# ocb03.net
KiCad netlist of a schematic drawn in EAGLE
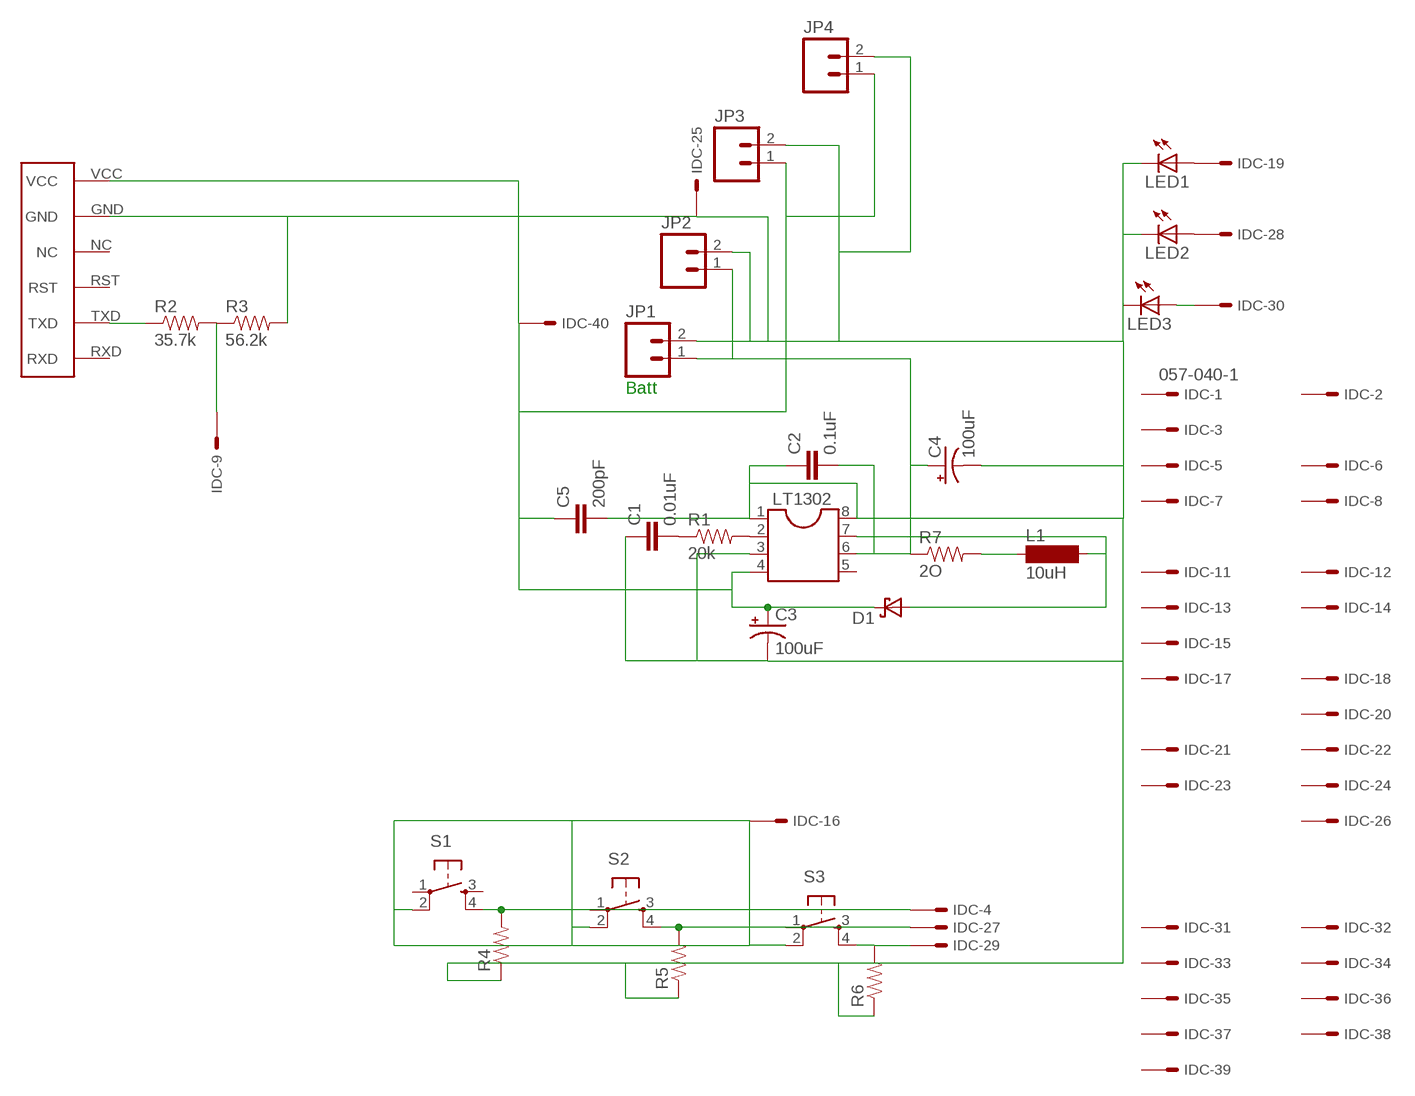
[diagram p0: schematic, sheet 1]

(export (version "E")
  (design (tool "Eeschema 10.0.6"))
  (components
    (comp (ref "C1")
      (value "0.01uF")
      (footprint "eagle-import:CAP-PTH-SMALL")
      (libsource (lib "eagle-import") (part "CAPPTH"))
    )
    (comp (ref "C2")
      (value "0.1uF")
      (footprint "eagle-import:CAP-PTH-SMALL")
      (libsource (lib "eagle-import") (part "CAPPTH"))
    )
    (comp (ref "C3")
      (value "100uF")
      (footprint "eagle-import:CPOL-RADIAL-100UF-25V")
      (libsource (lib "eagle-import") (part "CAP_POLPTH1"))
    )
    (comp (ref "C4")
      (value "100uF")
      (footprint "eagle-import:CPOL-RADIAL-100UF-25V")
      (libsource (lib "eagle-import") (part "CAP_POLPTH1"))
    )
    (comp (ref "C5")
      (value "200pF")
      (footprint "eagle-import:CAP-PTH-SMALL")
      (libsource (lib "eagle-import") (part "CAPPTH"))
    )
    (comp (ref "D1")
      (value "DS_E2L")
      (footprint "eagle-import:E2LINE")
      (libsource (lib "eagle-import") (part "DS_E2L"))
    )
    (comp (ref "IDC")
      (value "057-040-1")
      (footprint "eagle-import:057-040-1")
      (libsource (lib "eagle-import") (part "057-040-1"))
    )
    (comp (ref "JP1")
      (value "M02JST-PTH-2")
      (footprint "eagle-import:JST-2-PTH")
      (libsource (lib "eagle-import") (part "M02JST-PTH-2"))
    )
    (comp (ref "JP2")
      (value "M02JST-PTH-2")
      (footprint "eagle-import:JST-2-PTH")
      (libsource (lib "eagle-import") (part "M02JST-PTH-2"))
    )
    (comp (ref "JP3")
      (value "M02JST-PTH-2")
      (footprint "eagle-import:JST-2-PTH")
      (libsource (lib "eagle-import") (part "M02JST-PTH-2"))
    )
    (comp (ref "JP4")
      (value "M02JST-PTH-2")
      (footprint "eagle-import:JST-2-PTH")
      (libsource (lib "eagle-import") (part "M02JST-PTH-2"))
    )
    (comp (ref "L1")
      (value "10uH")
      (footprint "eagle-import:BS11")
      (libsource (lib "eagle-import") (part "BS11"))
    )
    (comp (ref "LED1")
      (value "LED5MM")
      (footprint "eagle-import:LED5MM")
      (libsource (lib "eagle-import") (part "LED5MM"))
    )
    (comp (ref "LED2")
      (value "LED5MM")
      (footprint "eagle-import:LED5MM")
      (libsource (lib "eagle-import") (part "LED5MM"))
    )
    (comp (ref "LED3")
      (value "LED5MM")
      (footprint "eagle-import:LED5MM")
      (libsource (lib "eagle-import") (part "LED5MM"))
    )
    (comp (ref "LT1302")
      (value "DIL8")
      (footprint "eagle-import:DIL08")
      (libsource (lib "eagle-import") (part "DIL8"))
    )
    (comp (ref "R1")
      (value "20k")
      (footprint "eagle-import:AXIAL-0.4")
      (libsource (lib "eagle-import") (part "RESISTORPTH-1/4W"))
    )
    (comp (ref "R2")
      (value "35.7k")
      (footprint "eagle-import:AXIAL-0.4")
      (libsource (lib "eagle-import") (part "RESISTORPTH-1/4W"))
    )
    (comp (ref "R3")
      (value "56.2k")
      (footprint "eagle-import:AXIAL-0.4")
      (libsource (lib "eagle-import") (part "RESISTORPTH-1/4W"))
    )
    (comp (ref "R4")
      (value "RESISTORPTH-1/4W")
      (footprint "eagle-import:AXIAL-0.4")
      (libsource (lib "eagle-import") (part "RESISTORPTH-1/4W"))
    )
    (comp (ref "R5")
      (value "RESISTORPTH-1/4W")
      (footprint "eagle-import:AXIAL-0.4")
      (libsource (lib "eagle-import") (part "RESISTORPTH-1/4W"))
    )
    (comp (ref "R6")
      (value "RESISTORPTH-1/4W")
      (footprint "eagle-import:AXIAL-0.4")
      (libsource (lib "eagle-import") (part "RESISTORPTH-1/4W"))
    )
    (comp (ref "R7")
      (value "2O")
      (footprint "eagle-import:AXIAL-0.4")
      (libsource (lib "eagle-import") (part "RESISTORPTH-1/4W"))
    )
    (comp (ref "S1")
      (value "TAC_SWITCHPTH")
      (footprint "eagle-import:TACTILE-PTH")
      (libsource (lib "eagle-import") (part "TAC_SWITCHPTH"))
    )
    (comp (ref "S2")
      (value "TAC_SWITCHPTH")
      (footprint "eagle-import:TACTILE-PTH")
      (libsource (lib "eagle-import") (part "TAC_SWITCHPTH"))
    )
    (comp (ref "S3")
      (value "TAC_SWITCHPTH")
      (footprint "eagle-import:TACTILE-PTH")
      (libsource (lib "eagle-import") (part "TAC_SWITCHPTH"))
    )
    (comp (ref "U$2")
      (value "SKYLAB_LAB")
      (footprint "eagle-import:SKYLAB_GPS")
      (libsource (lib "eagle-import") (part "SKYLAB_LAB"))
    )
  )
  (nets
    (net (code "1") (name "Net-(C3-+)") (class "Default")
      (node (ref "C3") (pin "1") (pinfunction "+_1") (pintype "passive"))
      (node (ref "C5") (pin "1") (pinfunction "1_1") (pintype "passive"))
      (node (ref "D1") (pin "1") (pinfunction "K_1") (pintype "passive"))
      (node (ref "IDC") (pin "40") (pinfunction "S_40") (pintype "passive"))
      (node (ref "JP3") (pin "1") (pinfunction "1_1") (pintype "passive"))
      (node (ref "JP4") (pin "1") (pinfunction "1_1") (pintype "passive"))
      (node (ref "LT1302") (pin "4") (pinfunction "4_4") (pintype "passive"))
      (node (ref "U$2") (pin "VCC") (pinfunction "VCC_VCC") (pintype "bidirectional"))
    )
    (net (code "2") (name "Net-(C3--)") (class "Default")
      (node (ref "C1") (pin "1") (pinfunction "1_1") (pintype "passive"))
      (node (ref "C2") (pin "1") (pinfunction "1_1") (pintype "passive"))
      (node (ref "C3") (pin "2") (pinfunction "-_2") (pintype "passive"))
      (node (ref "C4") (pin "2") (pinfunction "-_2") (pintype "passive"))
      (node (ref "C5") (pin "2") (pinfunction "2_2") (pintype "passive"))
      (node (ref "IDC") (pin "25") (pinfunction "S_25") (pintype "passive"))
      (node (ref "JP1") (pin "2") (pinfunction "2_2") (pintype "passive"))
      (node (ref "JP2") (pin "2") (pinfunction "2_2") (pintype "passive"))
      (node (ref "JP3") (pin "2") (pinfunction "2_2") (pintype "passive"))
      (node (ref "JP4") (pin "2") (pinfunction "2_2") (pintype "passive"))
      (node (ref "LED1") (pin "K") (pinfunction "C_K") (pintype "passive"))
      (node (ref "LED2") (pin "K") (pinfunction "C_K") (pintype "passive"))
      (node (ref "LED3") (pin "K") (pinfunction "C_K") (pintype "passive"))
      (node (ref "LT1302") (pin "1") (pinfunction "1_1") (pintype "passive"))
      (node (ref "LT1302") (pin "3") (pinfunction "3_3") (pintype "passive"))
      (node (ref "LT1302") (pin "8") (pinfunction "8_8") (pintype "passive"))
      (node (ref "R3") (pin "P$2") (pinfunction "2_P$2") (pintype "passive"))
      (node (ref "R4") (pin "P$1") (pinfunction "1_P$1") (pintype "passive"))
      (node (ref "R5") (pin "P$1") (pinfunction "1_P$1") (pintype "passive"))
      (node (ref "R6") (pin "P$1") (pinfunction "1_P$1") (pintype "passive"))
      (node (ref "U$2") (pin "GND") (pinfunction "GND_GND") (pintype "bidirectional"))
    )
    (net (code "3") (name "Net-(C4-+)") (class "Default")
      (node (ref "C2") (pin "2") (pinfunction "2_2") (pintype "passive"))
      (node (ref "C4") (pin "1") (pinfunction "+_1") (pintype "passive"))
      (node (ref "JP1") (pin "1") (pinfunction "1_1") (pintype "passive"))
      (node (ref "JP2") (pin "1") (pinfunction "1_1") (pintype "passive"))
      (node (ref "LT1302") (pin "6") (pinfunction "6_6") (pintype "passive"))
      (node (ref "R7") (pin "P$1") (pinfunction "1_P$1") (pintype "passive"))
    )
    (net (code "4") (name "Net-(D1-A)") (class "Default")
      (node (ref "D1") (pin "2") (pinfunction "A_2") (pintype "passive"))
      (node (ref "L1") (pin "2") (pinfunction "2_2") (pintype "passive"))
      (node (ref "LT1302") (pin "7") (pinfunction "7_7") (pintype "passive"))
    )
    (net (code "5") (name "Net-(IDCAH-S)") (class "Default")
      (node (ref "IDC") (pin "4") (pinfunction "S_4") (pintype "passive"))
      (node (ref "R4") (pin "P$2") (pinfunction "2_P$2") (pintype "passive"))
      (node (ref "S1") (pin "4") (pinfunction "4_4") (pintype "passive"))
    )
    (net (code "6") (name "Net-(IDCAN-S)") (class "Default")
      (node (ref "IDC") (pin "9") (pinfunction "S_9") (pintype "passive"))
      (node (ref "R2") (pin "P$2") (pinfunction "2_P$2") (pintype "passive"))
      (node (ref "R3") (pin "P$1") (pinfunction "1_P$1") (pintype "passive"))
    )
    (net (code "7") (name "Net-(IDCH-S)") (class "Default")
      (node (ref "IDC") (pin "16") (pinfunction "S_16") (pintype "passive"))
      (node (ref "S1") (pin "2") (pinfunction "2_2") (pintype "passive"))
      (node (ref "S2") (pin "2") (pinfunction "2_2") (pintype "passive"))
      (node (ref "S3") (pin "2") (pinfunction "2_2") (pintype "passive"))
    )
    (net (code "8") (name "Net-(IDCK-S)") (class "Default")
      (node (ref "IDC") (pin "19") (pinfunction "S_19") (pintype "passive"))
      (node (ref "LED1") (pin "A") (pinfunction "A_A") (pintype "passive"))
    )
    (net (code "9") (name "Net-(IDCT-S)") (class "Default")
      (node (ref "IDC") (pin "27") (pinfunction "S_27") (pintype "passive"))
      (node (ref "R5") (pin "P$2") (pinfunction "2_P$2") (pintype "passive"))
      (node (ref "S2") (pin "4") (pinfunction "4_4") (pintype "passive"))
    )
    (net (code "10") (name "Net-(IDCU-S)") (class "Default")
      (node (ref "IDC") (pin "28") (pinfunction "S_28") (pintype "passive"))
      (node (ref "LED2") (pin "A") (pinfunction "A_A") (pintype "passive"))
    )
    (net (code "11") (name "Net-(IDCV-S)") (class "Default")
      (node (ref "IDC") (pin "29") (pinfunction "S_29") (pintype "passive"))
      (node (ref "R6") (pin "P$2") (pinfunction "2_P$2") (pintype "passive"))
      (node (ref "S3") (pin "4") (pinfunction "4_4") (pintype "passive"))
    )
    (net (code "12") (name "Net-(IDCX-S)") (class "Default")
      (node (ref "IDC") (pin "30") (pinfunction "S_30") (pintype "passive"))
      (node (ref "LED3") (pin "A") (pinfunction "A_A") (pintype "passive"))
    )
    (net (code "13") (name "Net-(R1-1)") (class "Default")
      (node (ref "C1") (pin "2") (pinfunction "2_2") (pintype "passive"))
      (node (ref "R1") (pin "P$1") (pinfunction "1_P$1") (pintype "passive"))
    )
    (net (code "14") (name "Net-(R1-2)") (class "Default")
      (node (ref "LT1302") (pin "2") (pinfunction "2_2") (pintype "passive"))
      (node (ref "R1") (pin "P$2") (pinfunction "2_P$2") (pintype "passive"))
    )
    (net (code "15") (name "Net-(R2-1)") (class "Default")
      (node (ref "R2") (pin "P$1") (pinfunction "1_P$1") (pintype "passive"))
      (node (ref "U$2") (pin "TXD") (pinfunction "TXD_TXD") (pintype "bidirectional"))
    )
    (net (code "16") (name "Net-(R7-2)") (class "Default")
      (node (ref "L1") (pin "1") (pinfunction "1_1") (pintype "passive"))
      (node (ref "R7") (pin "P$2") (pinfunction "2_P$2") (pintype "passive"))
    )
    (net (code "17") (name "unconnected-(IDCA-S-Pad1)") (class "Default")
      (node (ref "IDC") (pin "1") (pinfunction "S_1") (pintype "passive"))
    )
    (net (code "18") (name "unconnected-(IDCAA-S-Pad33)") (class "Default")
      (node (ref "IDC") (pin "33") (pinfunction "S_33") (pintype "passive"))
    )
    (net (code "19") (name "unconnected-(IDCAB-S-Pad34)") (class "Default")
      (node (ref "IDC") (pin "34") (pinfunction "S_34") (pintype "passive"))
    )
    (net (code "20") (name "unconnected-(IDCAC-S-Pad35)") (class "Default")
      (node (ref "IDC") (pin "35") (pinfunction "S_35") (pintype "passive"))
    )
    (net (code "21") (name "unconnected-(IDCAD-S-Pad36)") (class "Default")
      (node (ref "IDC") (pin "36") (pinfunction "S_36") (pintype "passive"))
    )
    (net (code "22") (name "unconnected-(IDCAE-S-Pad37)") (class "Default")
      (node (ref "IDC") (pin "37") (pinfunction "S_37") (pintype "passive"))
    )
    (net (code "23") (name "unconnected-(IDCAF-S-Pad38)") (class "Default")
      (node (ref "IDC") (pin "38") (pinfunction "S_38") (pintype "passive"))
    )
    (net (code "24") (name "unconnected-(IDCAG-S-Pad39)") (class "Default")
      (node (ref "IDC") (pin "39") (pinfunction "S_39") (pintype "passive"))
    )
    (net (code "25") (name "unconnected-(IDCAJ-S-Pad5)") (class "Default")
      (node (ref "IDC") (pin "5") (pinfunction "S_5") (pintype "passive"))
    )
    (net (code "26") (name "unconnected-(IDCAK-S-Pad6)") (class "Default")
      (node (ref "IDC") (pin "6") (pinfunction "S_6") (pintype "passive"))
    )
    (net (code "27") (name "unconnected-(IDCAL-S-Pad7)") (class "Default")
      (node (ref "IDC") (pin "7") (pinfunction "S_7") (pintype "passive"))
    )
    (net (code "28") (name "unconnected-(IDCAM-S-Pad8)") (class "Default")
      (node (ref "IDC") (pin "8") (pinfunction "S_8") (pintype "passive"))
    )
    (net (code "29") (name "unconnected-(IDCC-S-Pad11)") (class "Default")
      (node (ref "IDC") (pin "11") (pinfunction "S_11") (pintype "passive"))
    )
    (net (code "30") (name "unconnected-(IDCD-S-Pad12)") (class "Default")
      (node (ref "IDC") (pin "12") (pinfunction "S_12") (pintype "passive"))
    )
    (net (code "31") (name "unconnected-(IDCE-S-Pad13)") (class "Default")
      (node (ref "IDC") (pin "13") (pinfunction "S_13") (pintype "passive"))
    )
    (net (code "32") (name "unconnected-(IDCF-S-Pad14)") (class "Default")
      (node (ref "IDC") (pin "14") (pinfunction "S_14") (pintype "passive"))
    )
    (net (code "33") (name "unconnected-(IDCG-S-Pad15)") (class "Default")
      (node (ref "IDC") (pin "15") (pinfunction "S_15") (pintype "passive"))
    )
    (net (code "34") (name "unconnected-(IDCI-S-Pad17)") (class "Default")
      (node (ref "IDC") (pin "17") (pinfunction "S_17") (pintype "passive"))
    )
    (net (code "35") (name "unconnected-(IDCJ-S-Pad18)") (class "Default")
      (node (ref "IDC") (pin "18") (pinfunction "S_18") (pintype "passive"))
    )
    (net (code "36") (name "unconnected-(IDCL-S-Pad2)") (class "Default")
      (node (ref "IDC") (pin "2") (pinfunction "S_2") (pintype "passive"))
    )
    (net (code "37") (name "unconnected-(IDCM-S-Pad20)") (class "Default")
      (node (ref "IDC") (pin "20") (pinfunction "S_20") (pintype "passive"))
    )
    (net (code "38") (name "unconnected-(IDCN-S-Pad21)") (class "Default")
      (node (ref "IDC") (pin "21") (pinfunction "S_21") (pintype "passive"))
    )
    (net (code "39") (name "unconnected-(IDCO-S-Pad22)") (class "Default")
      (node (ref "IDC") (pin "22") (pinfunction "S_22") (pintype "passive"))
    )
    (net (code "40") (name "unconnected-(IDCP-S-Pad23)") (class "Default")
      (node (ref "IDC") (pin "23") (pinfunction "S_23") (pintype "passive"))
    )
    (net (code "41") (name "unconnected-(IDCQ-S-Pad24)") (class "Default")
      (node (ref "IDC") (pin "24") (pinfunction "S_24") (pintype "passive"))
    )
    (net (code "42") (name "unconnected-(IDCS-S-Pad26)") (class "Default")
      (node (ref "IDC") (pin "26") (pinfunction "S_26") (pintype "passive"))
    )
    (net (code "43") (name "unconnected-(IDCW-S-Pad3)") (class "Default")
      (node (ref "IDC") (pin "3") (pinfunction "S_3") (pintype "passive"))
    )
    (net (code "44") (name "unconnected-(IDCY-S-Pad31)") (class "Default")
      (node (ref "IDC") (pin "31") (pinfunction "S_31") (pintype "passive"))
    )
    (net (code "45") (name "unconnected-(IDCZ-S-Pad32)") (class "Default")
      (node (ref "IDC") (pin "32") (pinfunction "S_32") (pintype "passive"))
    )
    (net (code "46") (name "unconnected-(LT1302-Pad5)") (class "Default")
      (node (ref "LT1302") (pin "5") (pinfunction "5_5") (pintype "passive"))
    )
    (net (code "47") (name "unconnected-(S1-Pad1)") (class "Default")
      (node (ref "S1") (pin "1") (pinfunction "1_1") (pintype "passive"))
    )
    (net (code "48") (name "unconnected-(S1-Pad3)") (class "Default")
      (node (ref "S1") (pin "3") (pinfunction "3_3") (pintype "passive"))
    )
    (net (code "49") (name "unconnected-(S2-Pad1)") (class "Default")
      (node (ref "S2") (pin "1") (pinfunction "1_1") (pintype "passive"))
    )
    (net (code "50") (name "unconnected-(S2-Pad3)") (class "Default")
      (node (ref "S2") (pin "3") (pinfunction "3_3") (pintype "passive"))
    )
    (net (code "51") (name "unconnected-(S3-Pad1)") (class "Default")
      (node (ref "S3") (pin "1") (pinfunction "1_1") (pintype "passive"))
    )
    (net (code "52") (name "unconnected-(S3-Pad3)") (class "Default")
      (node (ref "S3") (pin "3") (pinfunction "3_3") (pintype "passive"))
    )
    (net (code "53") (name "unconnected-(U$2-PadNC)") (class "Default")
      (node (ref "U$2") (pin "NC") (pinfunction "NC_NC") (pintype "bidirectional"))
    )
    (net (code "54") (name "unconnected-(U$2-PadRST)") (class "Default")
      (node (ref "U$2") (pin "RST") (pinfunction "RST_RST") (pintype "bidirectional"))
    )
    (net (code "55") (name "unconnected-(U$2-PadRXD)") (class "Default")
      (node (ref "U$2") (pin "RXD") (pinfunction "RXD_RXD") (pintype "bidirectional"))
    )
  )
)
